# STM32H753.net
KiCad netlist of a schematic drawn in Altium Designer
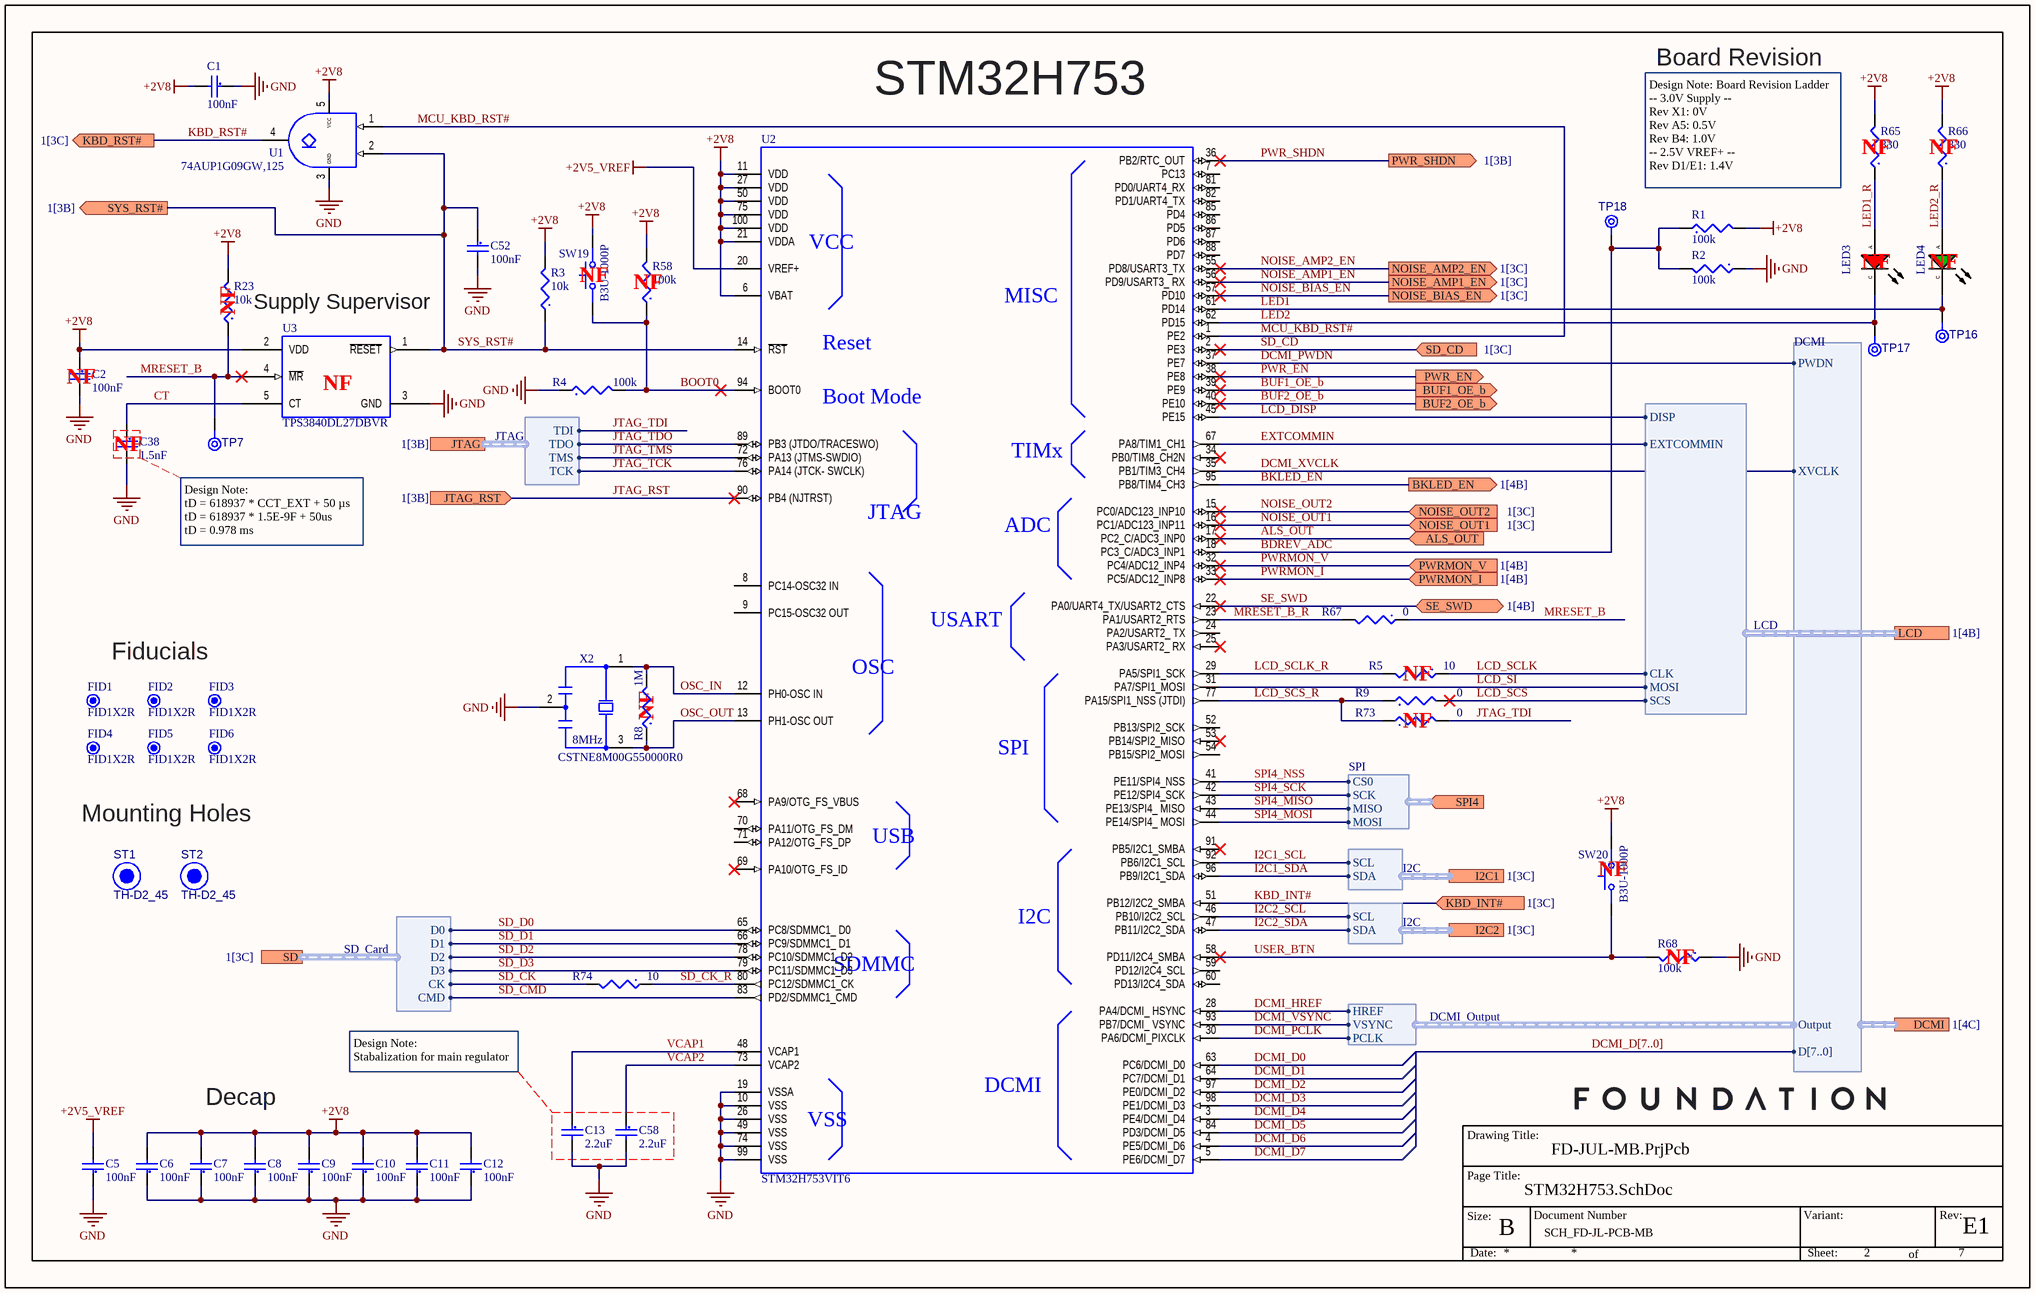
[diagram p0: STM32H753.SchDoc]

(export (version "E")
  (design (tool "Eeschema 10.0.6"))
  (components
    (comp (ref "C1")
      (value "CAP CER 0.1uF 16V 10% X7R 0402")
      (footprint "CAPC0402(1005)55_L")
      (description "0.1µF ±10% 16V Ceramic Capacitor X7R 0402 (1005 Metric)")
      (fields
        (field (name "CAPACITANCE") "100nF")
        (field (name "TOLERANCE") "10%")
        (field (name "VOLTAGE") "16V")
      )
      (libsource (lib "Altium Concord Pro on A365") (part "CAP-NP-2"))
    )
    (comp (ref "C2")
      (value "CAP CER 0.1uF 16V 10% X7R 0402")
      (footprint "CAPC0402(1005)55_L")
      (description "0.1µF ±10% 16V Ceramic Capacitor X7R 0402 (1005 Metric)")
      (fields
        (field (name "CAPACITANCE") "100nF")
        (field (name "VOLTAGE") "16V")
        (field (name "TOLERANCE") "10%")
      )
      (libsource (lib "Altium Concord Pro on A365") (part "CAP-NP-2"))
    )
    (comp (ref "C5")
      (value "CAP CER 0.1uF 16V 10% X7R 0402")
      (footprint "CAPC0402(1005)55_L")
      (description "0.1µF ±10% 16V Ceramic Capacitor X7R 0402 (1005 Metric)")
      (fields
        (field (name "CAPACITANCE") "100nF")
        (field (name "TOLERANCE") "10%")
        (field (name "VOLTAGE") "16V")
      )
      (libsource (lib "Altium Concord Pro on A365") (part "CAP-NP-2"))
    )
    (comp (ref "C6")
      (value "CAP CER 0.1uF 16V 10% X7R 0402")
      (footprint "CAPC0402(1005)55_L")
      (description "0.1µF ±10% 16V Ceramic Capacitor X7R 0402 (1005 Metric)")
      (fields
        (field (name "CAPACITANCE") "100nF")
        (field (name "TOLERANCE") "10%")
        (field (name "VOLTAGE") "16V")
      )
      (libsource (lib "Altium Concord Pro on A365") (part "CAP-NP-2"))
    )
    (comp (ref "C7")
      (value "CAP CER 0.1uF 16V 10% X7R 0402")
      (footprint "CAPC0402(1005)55_L")
      (description "0.1µF ±10% 16V Ceramic Capacitor X7R 0402 (1005 Metric)")
      (fields
        (field (name "CAPACITANCE") "100nF")
        (field (name "TOLERANCE") "10%")
        (field (name "VOLTAGE") "16V")
      )
      (libsource (lib "Altium Concord Pro on A365") (part "CAP-NP-2"))
    )
    (comp (ref "C8")
      (value "CAP CER 0.1uF 16V 10% X7R 0402")
      (footprint "CAPC0402(1005)55_L")
      (description "0.1µF ±10% 16V Ceramic Capacitor X7R 0402 (1005 Metric)")
      (fields
        (field (name "CAPACITANCE") "100nF")
        (field (name "TOLERANCE") "10%")
        (field (name "VOLTAGE") "16V")
      )
      (libsource (lib "Altium Concord Pro on A365") (part "CAP-NP-2"))
    )
    (comp (ref "C9")
      (value "CAP CER 0.1uF 16V 10% X7R 0402")
      (footprint "CAPC0402(1005)55_L")
      (description "0.1µF ±10% 16V Ceramic Capacitor X7R 0402 (1005 Metric)")
      (fields
        (field (name "CAPACITANCE") "100nF")
        (field (name "TOLERANCE") "10%")
        (field (name "VOLTAGE") "16V")
      )
      (libsource (lib "Altium Concord Pro on A365") (part "CAP-NP-2"))
    )
    (comp (ref "C10")
      (value "CAP CER 0.1uF 16V 10% X7R 0402")
      (footprint "CAPC0402(1005)55_L")
      (description "0.1µF ±10% 16V Ceramic Capacitor X7R 0402 (1005 Metric)")
      (fields
        (field (name "CAPACITANCE") "100nF")
        (field (name "TOLERANCE") "10%")
        (field (name "VOLTAGE") "16V")
      )
      (libsource (lib "Altium Concord Pro on A365") (part "CAP-NP-2"))
    )
    (comp (ref "C11")
      (value "CAP CER 0.1uF 16V 10% X7R 0402")
      (footprint "CAPC0402(1005)55_L")
      (description "0.1µF ±10% 16V Ceramic Capacitor X7R 0402 (1005 Metric)")
      (fields
        (field (name "CAPACITANCE") "100nF")
        (field (name "TOLERANCE") "10%")
        (field (name "VOLTAGE") "16V")
      )
      (libsource (lib "Altium Concord Pro on A365") (part "CAP-NP-2"))
    )
    (comp (ref "C12")
      (value "CAP CER 0.1uF 16V 10% X7R 0402")
      (footprint "CAPC0402(1005)55_L")
      (description "0.1µF ±10% 16V Ceramic Capacitor X7R 0402 (1005 Metric)")
      (fields
        (field (name "CAPACITANCE") "100nF")
        (field (name "TOLERANCE") "10%")
        (field (name "VOLTAGE") "16V")
      )
      (libsource (lib "Altium Concord Pro on A365") (part "CAP-NP-2"))
    )
    (comp (ref "C13")
      (value "CAP CER 2.2uF 6.3V 10% X5R 0402")
      (footprint "CAPC0402(1005)55_L")
      (description "2.2µF ±10% 6.3V Ceramic Capacitor X5R 0402 (1005 Metric)")
      (fields (field (name "CAPACITANCE") "2.2uF") (field (name "TOLERANCE") "10%"))
      (libsource (lib "Altium Concord Pro on A365") (part "CAP-NP-2"))
    )
    (comp (ref "C38")
      (value "CAP CER 1500pF 50V 10% X7R 0402")
      (footprint "CAPC0402(1005)55_L")
      (description "1500pF ±10% 50V Ceramic Capacitor X7R 0402 (1005 Metric)")
      (fields
        (field (name "CAPACITANCE") "1.5nF")
        (field (name "VOLTAGE") "50V")
        (field (name "TOLERANCE") "10%")
      )
      (libsource (lib "Altium Concord Pro on A365") (part "CAP-NP-2"))
    )
    (comp (ref "C52")
      (value "CAP CER 0.1uF 16V 10% X7R 0402")
      (footprint "CAPC0402(1005)55_L")
      (description "0.1µF ±10% 16V Ceramic Capacitor X7R 0402 (1005 Metric)")
      (fields
        (field (name "CAPACITANCE") "100nF")
        (field (name "VOLTAGE") "16V")
        (field (name "TOLERANCE") "10%")
      )
      (libsource (lib "Altium Concord Pro on A365") (part "CAP-NP-2"))
    )
    (comp (ref "C58")
      (value "CAP CER 2.2uF 6.3V 10% X5R 0402")
      (footprint "CAPC0402(1005)55_L")
      (description "2.2µF ±10% 6.3V Ceramic Capacitor X5R 0402 (1005 Metric)")
      (fields (field (name "CAPACITANCE") "2.2uF") (field (name "TOLERANCE") "10%"))
      (libsource (lib "Altium Concord Pro on A365") (part "CAP-NP-2"))
    )
    (comp (ref "FID1")
      (value "FID1X2R")
      (footprint "FID1X2R")
      (description "Fiducial - Round 1x2mm")
      (libsource (lib "Altium Concord Pro on A365") (part "FID-R-1"))
    )
    (comp (ref "FID2")
      (value "FID1X2R")
      (footprint "FID1X2R")
      (description "Fiducial - Round 1x2mm")
      (libsource (lib "Altium Concord Pro on A365") (part "FID-R-1"))
    )
    (comp (ref "FID3")
      (value "FID1X2R")
      (footprint "FID1X2R")
      (description "Fiducial - Round 1x2mm")
      (libsource (lib "Altium Concord Pro on A365") (part "FID-R-1"))
    )
    (comp (ref "FID4")
      (value "FID1X2R")
      (footprint "FID1X2R")
      (description "Fiducial - Round 1x2mm")
      (libsource (lib "Altium Concord Pro on A365") (part "FID-R-1"))
    )
    (comp (ref "FID5")
      (value "FID1X2R")
      (footprint "FID1X2R")
      (description "Fiducial - Round 1x2mm")
      (libsource (lib "Altium Concord Pro on A365") (part "FID-R-1"))
    )
    (comp (ref "FID6")
      (value "FID1X2R")
      (footprint "FID1X2R")
      (description "Fiducial - Round 1x2mm")
      (libsource (lib "Altium Concord Pro on A365") (part "FID-R-1"))
    )
    (comp (ref "LED3")
      (value "LTST-C191KRKT")
      (footprint "LEDC0603(1608)65_L")
      (description "Red 631nm LED Indication - Discrete 2V 0603 (1608 Metric)")
      (fields (field (name "VOLTAGE") "2V"))
      (libsource (lib "Altium Concord Pro on A365") (part "LED-RED-AC-2"))
    )
    (comp (ref "LED4")
      (value "LTST-C191KGKT")
      (footprint "LEDC0603(1608)65_L")
      (description "Green 571nm LED Indication - Discrete 2V 0603 (1608 Metric)")
      (libsource (lib "Altium Concord Pro on A365") (part "LED-GREEN-AC-2"))
    )
    (comp (ref "R1")
      (value "RES 100K 1/16W 1% 0402")
      (footprint "RESC0402(1005)_L")
      (description "100 kOhms ±1% 0.063W, 1/16W Chip Resistor 0402 (1005 Metric) Automotive AEC-Q200 Thick Film")
      (fields (field (name "RESISTANCE") "100k") (field (name "TOLERANCE") "1%"))
      (libsource (lib "Altium Concord Pro on A365") (part "RES-2"))
    )
    (comp (ref "R2")
      (value "RES 100K 1/16W 1% 0402")
      (footprint "RESC0402(1005)_L")
      (description "100 kOhms ±1% 0.063W, 1/16W Chip Resistor 0402 (1005 Metric) Automotive AEC-Q200 Thick Film")
      (fields (field (name "RESISTANCE") "100k") (field (name "TOLERANCE") "1%"))
      (libsource (lib "Altium Concord Pro on A365") (part "RES-2"))
    )
    (comp (ref "R3")
      (value "RES 10K 1/16W 1% 0402")
      (footprint "RESC0402(1005)_L")
      (description "10 kOhms ±1% 0.063W, 1/16W Chip Resistor 0402 (1005 Metric)")
      (fields (field (name "RESISTANCE") "10k") (field (name "TOLERANCE") "1%"))
      (libsource (lib "Altium Concord Pro on A365") (part "RES-2"))
    )
    (comp (ref "R4")
      (value "RES 100K 1/16W 1% 0402")
      (footprint "RESC0402(1005)_L")
      (description "100 kOhms ±1% 0.063W, 1/16W Chip Resistor 0402 (1005 Metric) Automotive AEC-Q200 Thick Film")
      (fields (field (name "RESISTANCE") "100k") (field (name "TOLERANCE") "1%"))
      (libsource (lib "Altium Concord Pro on A365") (part "RES-2"))
    )
    (comp (ref "R5")
      (value "RES 10 OHM 1/16W 1% 0402")
      (footprint "RESC0402(1005)_L")
      (description "10 Ohms ±1% 0.063W, 1/16W Chip Resistor 0402 (1005 Metric)")
      (fields (field (name "RESISTANCE") "10") (field (name "TOLERANCE") "1%"))
      (libsource (lib "Altium Concord Pro on A365") (part "RES-2"))
    )
    (comp (ref "R8")
      (value "RES 1M 1/16W 1% 0402")
      (footprint "RESC0402(1005)_L")
      (description "1 MOhms ±1% 0.063W, 1/16W Chip Resistor 0402 (1005 Metric)")
      (fields (field (name "RESISTANCE") "1M") (field (name "TOLERANCE") "1%"))
      (libsource (lib "Altium Concord Pro on A365") (part "RES-2"))
    )
    (comp (ref "R9")
      (value "RES 0 OHM JUMPER 1/16W 0402")
      (footprint "RESC0402(1005)_L")
      (description "0 Ohms Jumper 0.063W, 1/16W Chip Resistor 0402 (1005 Metric)")
      (fields (field (name "RESISTANCE") "0") (field (name "TOLERANCE") "5%"))
      (libsource (lib "Altium Concord Pro on A365") (part "RES-2"))
    )
    (comp (ref "R23")
      (value "RES 10K 1/16W 1% 0402")
      (footprint "RESC0402(1005)_L")
      (description "10 kOhms ±1% 0.063W, 1/16W Chip Resistor 0402 (1005 Metric)")
      (fields (field (name "RESISTANCE") "10k") (field (name "TOLERANCE") "1%"))
      (libsource (lib "Altium Concord Pro on A365") (part "RES-2"))
    )
    (comp (ref "R58")
      (value "RES 100K 1/16W 1% 0402")
      (footprint "RESC0402(1005)_L")
      (description "100 kOhms ±1% 0.063W, 1/16W Chip Resistor 0402 (1005 Metric) Automotive AEC-Q200 Thick Film")
      (fields (field (name "RESISTANCE") "100k") (field (name "TOLERANCE") "1%"))
      (libsource (lib "Altium Concord Pro on A365") (part "RES-2"))
    )
    (comp (ref "R65")
      (value "RES 330 OHM 1/16W 1% 0402")
      (footprint "RESC0402(1005)_L")
      (description "330 Ohms ±1% 0.063W, 1/16W Chip Resistor 0402 (1005 Metric) Moisture Resistant Thick Film")
      (fields (field (name "RESISTANCE") "330") (field (name "TOLERANCE") "1%"))
      (libsource (lib "Altium Concord Pro on A365") (part "RES-2"))
    )
    (comp (ref "R66")
      (value "RES 330 OHM 1/16W 1% 0402")
      (footprint "RESC0402(1005)_L")
      (description "330 Ohms ±1% 0.063W, 1/16W Chip Resistor 0402 (1005 Metric) Moisture Resistant Thick Film")
      (fields (field (name "RESISTANCE") "330") (field (name "TOLERANCE") "1%"))
      (libsource (lib "Altium Concord Pro on A365") (part "RES-2"))
    )
    (comp (ref "R67")
      (value "RES 0 OHM JUMPER 1/16W 0402")
      (footprint "RESC0402(1005)_L")
      (description "0 Ohms Jumper 0.063W, 1/16W Chip Resistor 0402 (1005 Metric)")
      (fields (field (name "RESISTANCE") "0") (field (name "TOLERANCE") "5%"))
      (libsource (lib "Altium Concord Pro on A365") (part "RES-2"))
    )
    (comp (ref "R68")
      (value "RES 100K 1/16W 1% 0402")
      (footprint "RESC0402(1005)_L")
      (description "100 kOhms ±1% 0.063W, 1/16W Chip Resistor 0402 (1005 Metric) Automotive AEC-Q200 Thick Film")
      (fields (field (name "RESISTANCE") "100k") (field (name "TOLERANCE") "1%"))
      (libsource (lib "Altium Concord Pro on A365") (part "RES-2"))
    )
    (comp (ref "R73")
      (value "RES 0 OHM JUMPER 1/16W 0402")
      (footprint "RESC0402(1005)_L")
      (description "0 Ohms Jumper 0.063W, 1/16W Chip Resistor 0402 (1005 Metric)")
      (fields (field (name "RESISTANCE") "0") (field (name "TOLERANCE") "5%"))
      (libsource (lib "Altium Concord Pro on A365") (part "RES-2"))
    )
    (comp (ref "R74")
      (value "RES 10 OHM 1/16W 1% 0402")
      (footprint "RESC0402(1005)_L")
      (description "10 Ohms ±1% 0.063W, 1/16W Chip Resistor 0402 (1005 Metric)")
      (fields (field (name "RESISTANCE") "10") (field (name "TOLERANCE") "1%"))
      (libsource (lib "Altium Concord Pro on A365") (part "RES-2"))
    )
    (comp (ref "ST1")
      (value "TH-D2_45")
      (footprint "TH-D2_54")
      (description "Through Hole, Drill 2.54mm")
      (libsource (lib "Altium Concord Pro on A365") (part "TH"))
    )
    (comp (ref "ST2")
      (value "TH-D2_45")
      (footprint "TH-D2_54")
      (description "Through Hole, Drill 2.54mm")
      (libsource (lib "Altium Concord Pro on A365") (part "TH"))
    )
    (comp (ref "SW19")
      (value "B3U-1000P")
      (footprint "OMRON-B3U-1000P-2_V")
      (description "Tactile Switch SPST-NO Top Actuated Surface Mount")
      (libsource (lib "Altium Concord Pro on A365") (part "TAC-2"))
    )
    (comp (ref "SW20")
      (value "B3U-1000P")
      (footprint "OMRON-B3U-1000P-2_V")
      (description "Tactile Switch SPST-NO Top Actuated Surface Mount")
      (libsource (lib "Altium Concord Pro on A365") (part "TAC-2"))
    )
    (comp (ref "TP7")
      (value "TPAD8R")
      (footprint "TP08R")
      (description "0.8mm round")
      (libsource (lib "Altium Concord Pro on A365") (part "TP-R-1"))
    )
    (comp (ref "TP16")
      (value "TPAD8R")
      (footprint "TP08R")
      (description "0.8mm round")
      (libsource (lib "Altium Concord Pro on A365") (part "TP-R-1"))
    )
    (comp (ref "TP17")
      (value "TPAD8R")
      (footprint "TP08R")
      (description "0.8mm round")
      (libsource (lib "Altium Concord Pro on A365") (part "TP-R-1"))
    )
    (comp (ref "TP18")
      (value "TPAD8R")
      (footprint "TP08R")
      (description "0.8mm round")
      (libsource (lib "Altium Concord Pro on A365") (part "TP-R-1"))
    )
    (comp (ref "U1")
      (value "74AUP1G09GW,125")
      (footprint "NEXP - TSSOP-5_L")
      (description "IC GATE AND 1CH 2-INP 5TSSOP")
      (libsource (lib "Altium Concord Pro on A365") (part "AND-2-12-4-3-OD"))
    )
    (comp (ref "U2")
      (value "STM32H753VIT6")
      (footprint "STM - LQFP-100_L")
      (description "ARM® Cortex®-M7 STM32H7 Microcontroller IC 32-Bit 480MHz 2MB (2M x 8) FLASH 100-LQFP (14x14)")
      (libsource (lib "Altium Concord Pro on A365") (part "STM32H743VIT6"))
    )
    (comp (ref "U3")
      (value "TPS3840DL27DBVR")
      (footprint "SOT-23-5(95)_L")
      (description "Supervisor 2.7V Open Drain 1 Channel SOT-23-5")
      (libsource (lib "Altium Concord Pro on A365") (part "TPS3840DL"))
    )
    (comp (ref "X2")
      (value "CSTNE8M00G550000R0")
      (footprint "MURA - CSTNE_V")
      (description "8MHz Ceramic Resonator Built in Capacitor 33pF ±0.2% 40 Ohms -40°C ~ 85°C Surface Mount")
      (fields (field (name "FREQUENCY") "8MHz"))
      (libsource (lib "Altium Concord Pro on A365") (part "XTAL-3-13-INTC"))
    )
  )
  (nets
    (net (code "8") (name "+2V5_VREF") (class "Default")
      (node (ref "C5") (pin "2") (pinfunction "2_2") (pintype "passive"))
      (node (ref "U2") (pin "20") (pinfunction "VREF+_20") (pintype "power_in"))
    )
    (net (code "9") (name "+2V8") (class "Default")
      (node (ref "C1") (pin "2") (pinfunction "2_2") (pintype "passive"))
      (node (ref "C10") (pin "2") (pinfunction "2_2") (pintype "passive"))
      (node (ref "C11") (pin "2") (pinfunction "2_2") (pintype "passive"))
      (node (ref "C12") (pin "2") (pinfunction "2_2") (pintype "passive"))
      (node (ref "C2") (pin "1") (pinfunction "1_1") (pintype "passive"))
      (node (ref "C6") (pin "2") (pinfunction "2_2") (pintype "passive"))
      (node (ref "C7") (pin "2") (pinfunction "2_2") (pintype "passive"))
      (node (ref "C8") (pin "2") (pinfunction "2_2") (pintype "passive"))
      (node (ref "C9") (pin "2") (pinfunction "2_2") (pintype "passive"))
      (node (ref "R1") (pin "2") (pinfunction "2_2") (pintype "passive"))
      (node (ref "R23") (pin "2") (pinfunction "2_2") (pintype "passive"))
      (node (ref "R3") (pin "2") (pinfunction "2_2") (pintype "passive"))
      (node (ref "R58") (pin "2") (pinfunction "2_2") (pintype "passive"))
      (node (ref "R65") (pin "2") (pinfunction "2_2") (pintype "passive"))
      (node (ref "R66") (pin "2") (pinfunction "2_2") (pintype "passive"))
      (node (ref "SW19") (pin "2") (pinfunction "2_2") (pintype "passive"))
      (node (ref "SW20") (pin "2") (pinfunction "2_2") (pintype "passive"))
      (node (ref "U1") (pin "5") (pinfunction "VCC_5") (pintype "passive"))
      (node (ref "U2") (pin "100") (pinfunction "VDD_100") (pintype "power_in"))
      (node (ref "U2") (pin "11") (pinfunction "VDD_11") (pintype "power_in"))
      (node (ref "U2") (pin "21") (pinfunction "VDDA_21") (pintype "power_in"))
      (node (ref "U2") (pin "27") (pinfunction "VDD_27") (pintype "power_in"))
      (node (ref "U2") (pin "50") (pinfunction "VDD_50") (pintype "power_in"))
      (node (ref "U2") (pin "6") (pinfunction "VBAT_6") (pintype "power_in"))
      (node (ref "U2") (pin "75") (pinfunction "VDD_75") (pintype "power_in"))
      (node (ref "U3") (pin "2") (pinfunction "VDD_2") (pintype "power_in"))
    )
    (net (code "10") (name "/ALS_OUT") (class "Default")
      (node (ref "U2") (pin "17") (pinfunction "PC2_C/ADC3_INP0_17") (pintype "bidirectional+no_connect"))
    )
    (net (code "11") (name "/BDREV_ADC") (class "Default")
      (node (ref "R1") (pin "1") (pinfunction "1_1") (pintype "passive"))
      (node (ref "R2") (pin "2") (pinfunction "2_2") (pintype "passive"))
      (node (ref "TP18") (pin "1") (pinfunction "TP_1") (pintype "passive"))
      (node (ref "U2") (pin "18") (pinfunction "PC3_C/ADC3_INP1_18") (pintype "bidirectional"))
    )
    (net (code "12") (name "/BKLED_EN") (class "Default")
      (node (ref "U2") (pin "95") (pinfunction "PB8/TIM4_CH3_95") (pintype "output"))
    )
    (net (code "13") (name "/BOOT0") (class "Default")
      (node (ref "R4") (pin "2") (pinfunction "2_2") (pintype "passive"))
      (node (ref "R58") (pin "1") (pinfunction "1_1") (pintype "passive"))
      (node (ref "SW19") (pin "1") (pinfunction "1_1") (pintype "passive"))
      (node (ref "U2") (pin "94") (pinfunction "BOOT0_94") (pintype "input"))
    )
    (net (code "14") (name "/BUF1_OE_b") (class "Default")
      (node (ref "U2") (pin "39") (pinfunction "PE9_39") (pintype "bidirectional+no_connect"))
    )
    (net (code "15") (name "/BUF2_OE_b") (class "Default")
      (node (ref "U2") (pin "40") (pinfunction "PE10_40") (pintype "bidirectional+no_connect"))
    )
    (net (code "16") (name "/CT") (class "Default")
      (node (ref "C38") (pin "1") (pinfunction "1_1") (pintype "passive"))
      (node (ref "U3") (pin "5") (pinfunction "CT_5") (pintype "passive"))
    )
    (net (code "17") (name "/DCMI_D0") (class "Default")
      (node (ref "U2") (pin "63") (pinfunction "PC6/DCMI_D0_63") (pintype "input"))
    )
    (net (code "18") (name "/DCMI_D1") (class "Default")
      (node (ref "U2") (pin "64") (pinfunction "PC7/DCMI_D1_64") (pintype "input"))
    )
    (net (code "19") (name "/DCMI_D2") (class "Default")
      (node (ref "U2") (pin "97") (pinfunction "PE0/DCMI_D2_97") (pintype "input"))
    )
    (net (code "20") (name "/DCMI_D3") (class "Default")
      (node (ref "U2") (pin "98") (pinfunction "PE1/DCMI_D3_98") (pintype "input"))
    )
    (net (code "21") (name "/DCMI_D4") (class "Default")
      (node (ref "U2") (pin "3") (pinfunction "PE4/DCMI_D4_3") (pintype "input"))
    )
    (net (code "22") (name "/DCMI_D5") (class "Default")
      (node (ref "U2") (pin "84") (pinfunction "PD3/DCMI_D5_84") (pintype "input"))
    )
    (net (code "23") (name "/DCMI_D6") (class "Default")
      (node (ref "U2") (pin "4") (pinfunction "PE5/DCMI_D6_4") (pintype "input"))
    )
    (net (code "24") (name "/DCMI_D7") (class "Default")
      (node (ref "U2") (pin "5") (pinfunction "PE6/DCMI_D7_5") (pintype "input"))
    )
    (net (code "25") (name "/DCMI_HREF") (class "Default")
      (node (ref "U2") (pin "28") (pinfunction "PA4/DCMI__HSYNC_28") (pintype "input"))
    )
    (net (code "26") (name "/DCMI_PCLK") (class "Default")
      (node (ref "U2") (pin "30") (pinfunction "PA6/DCMI_PIXCLK_30") (pintype "input"))
    )
    (net (code "27") (name "/DCMI_PWDN") (class "Default")
      (node (ref "U2") (pin "37") (pinfunction "PE7_37") (pintype "bidirectional"))
    )
    (net (code "28") (name "/DCMI_VSYNC") (class "Default")
      (node (ref "U2") (pin "93") (pinfunction "PB7/DCMI__VSYNC_93") (pintype "input"))
    )
    (net (code "29") (name "/DCMI_XVCLK") (class "Default")
      (node (ref "U2") (pin "35") (pinfunction "PB1/TIM3_CH4_35") (pintype "output"))
    )
    (net (code "31") (name "/EXTCOMMIN") (class "Default")
      (node (ref "U2") (pin "67") (pinfunction "PA8/TIM1_CH1_67") (pintype "output"))
    )
    (net (code "32") (name "/I2C1_SCL") (class "Default")
      (node (ref "U2") (pin "92") (pinfunction "PB6/I2C1_SCL_92") (pintype "output"))
    )
    (net (code "33") (name "/I2C1_SDA") (class "Default")
      (node (ref "U2") (pin "96") (pinfunction "PB9/I2C1_SDA_96") (pintype "bidirectional"))
    )
    (net (code "34") (name "/I2C2_SCL") (class "Default")
      (node (ref "U2") (pin "46") (pinfunction "PB10/I2C2_SCL_46") (pintype "output"))
    )
    (net (code "35") (name "/I2C2_SDA") (class "Default")
      (node (ref "U2") (pin "47") (pinfunction "PB11/I2C2_SDA_47") (pintype "bidirectional"))
    )
    (net (code "36") (name "/JTAG_RST") (class "Default")
      (node (ref "U2") (pin "90") (pinfunction "PB4_(NJTRST)_90") (pintype "bidirectional+no_connect"))
    )
    (net (code "37") (name "/JTAG_TCK") (class "Default")
      (node (ref "U2") (pin "76") (pinfunction "PA14_(JTCK-_SWCLK)_76") (pintype "bidirectional"))
    )
    (net (code "38") (name "/JTAG_TDI") (class "Default")
      (node (ref "R73") (pin "2") (pinfunction "2_2") (pintype "passive"))
    )
    (net (code "39") (name "/JTAG_TDO") (class "Default")
      (node (ref "U2") (pin "89") (pinfunction "PB3_(JTDO/TRACESWO)_89") (pintype "bidirectional"))
    )
    (net (code "40") (name "/JTAG_TMS") (class "Default")
      (node (ref "U2") (pin "72") (pinfunction "PA13_(JTMS-SWDIO)_72") (pintype "bidirectional"))
    )
    (net (code "41") (name "/KBD_INT#") (class "Default")
      (node (ref "U2") (pin "51") (pinfunction "PB12/I2C2_SMBA_51") (pintype "input"))
    )
    (net (code "42") (name "/KBD_RST#") (class "Default")
      (node (ref "U1") (pin "4") (pinfunction "4_4") (pintype "open_collector"))
    )
    (net (code "43") (name "/LCD_DISP") (class "Default")
      (node (ref "U2") (pin "45") (pinfunction "PE15_45") (pintype "bidirectional"))
    )
    (net (code "44") (name "/LCD_SCLK") (class "Default")
      (node (ref "R5") (pin "1") (pinfunction "1_1") (pintype "passive"))
    )
    (net (code "45") (name "/LCD_SCLK_R") (class "Default")
      (node (ref "R5") (pin "2") (pinfunction "2_2") (pintype "passive"))
      (node (ref "U2") (pin "29") (pinfunction "PA5/SPI1_SCK_29") (pintype "output"))
    )
    (net (code "46") (name "/LCD_SCS") (class "Default")
      (node (ref "R9") (pin "2") (pinfunction "2_2") (pintype "passive+no_connect"))
    )
    (net (code "47") (name "/LCD_SCS_R") (class "Default")
      (node (ref "R73") (pin "1") (pinfunction "1_1") (pintype "passive"))
      (node (ref "R9") (pin "1") (pinfunction "1_1") (pintype "passive"))
      (node (ref "U2") (pin "77") (pinfunction "PA15/SPI1_NSS_(JTDI)_77") (pintype "output"))
    )
    (net (code "48") (name "/LCD_SI") (class "Default")
      (node (ref "U2") (pin "31") (pinfunction "PA7/SPI1_MOSI_31") (pintype "output"))
    )
    (net (code "49") (name "/LED1") (class "Default")
      (node (ref "LED4") (pin "C") (pinfunction "C_C") (pintype "passive"))
      (node (ref "TP16") (pin "1") (pinfunction "TP_1") (pintype "passive"))
      (node (ref "U2") (pin "61") (pinfunction "PD14_61") (pintype "bidirectional"))
    )
    (net (code "50") (name "/LED1_R") (class "Default")
      (node (ref "LED3") (pin "A") (pinfunction "A_A") (pintype "passive"))
      (node (ref "R65") (pin "1") (pinfunction "1_1") (pintype "passive"))
    )
    (net (code "51") (name "/LED2") (class "Default")
      (node (ref "LED3") (pin "C") (pinfunction "C_C") (pintype "passive"))
      (node (ref "TP17") (pin "1") (pinfunction "TP_1") (pintype "passive"))
      (node (ref "U2") (pin "62") (pinfunction "PD15_62") (pintype "bidirectional"))
    )
    (net (code "52") (name "/LED2_R") (class "Default")
      (node (ref "LED4") (pin "A") (pinfunction "A_A") (pintype "passive"))
      (node (ref "R66") (pin "1") (pinfunction "1_1") (pintype "passive"))
    )
    (net (code "53") (name "/MCU_KBD_RST#") (class "Default")
      (node (ref "U1") (pin "1") (pinfunction "1_1") (pintype "input"))
      (node (ref "U2") (pin "1") (pinfunction "PE2_1") (pintype "bidirectional"))
    )
    (net (code "54") (name "/MRESET_B") (class "Default")
      (node (ref "R23") (pin "1") (pinfunction "1_1") (pintype "passive"))
      (node (ref "R67") (pin "1") (pinfunction "1_1") (pintype "passive"))
      (node (ref "TP7") (pin "1") (pinfunction "TP_1") (pintype "passive"))
      (node (ref "U3") (pin "4") (pinfunction "~{MR}_4") (pintype "input"))
    )
    (net (code "55") (name "/MRESET_B_R") (class "Default")
      (node (ref "R67") (pin "2") (pinfunction "2_2") (pintype "passive"))
      (node (ref "U2") (pin "23") (pinfunction "PA1/USART2_RTS_23") (pintype "output"))
    )
    (net (code "56") (name "/NOISE_AMP1_EN") (class "Default")
      (node (ref "U2") (pin "56") (pinfunction "PD9/USART3__RX_56") (pintype "bidirectional+no_connect"))
    )
    (net (code "57") (name "/NOISE_AMP2_EN") (class "Default")
      (node (ref "U2") (pin "55") (pinfunction "PD8/USART3_TX_55") (pintype "bidirectional+no_connect"))
    )
    (net (code "58") (name "/NOISE_BIAS_EN") (class "Default")
      (node (ref "U2") (pin "57") (pinfunction "PD10_57") (pintype "bidirectional+no_connect"))
    )
    (net (code "59") (name "/NOISE_OUT1") (class "Default")
      (node (ref "U2") (pin "16") (pinfunction "PC1/ADC123_INP11_16") (pintype "bidirectional+no_connect"))
    )
    (net (code "60") (name "/NOISE_OUT2") (class "Default")
      (node (ref "U2") (pin "15") (pinfunction "PC0/ADC123_INP10_15") (pintype "bidirectional+no_connect"))
    )
    (net (code "61") (name "/OSC_IN") (class "Default")
      (node (ref "R8") (pin "2") (pinfunction "2_2") (pintype "passive"))
      (node (ref "U2") (pin "12") (pinfunction "PH0-OSC_IN_12") (pintype "passive"))
      (node (ref "X2") (pin "1") (pinfunction "1_1") (pintype "passive"))
    )
    (net (code "62") (name "/OSC_OUT") (class "Default")
      (node (ref "R8") (pin "1") (pinfunction "1_1") (pintype "passive"))
      (node (ref "U2") (pin "13") (pinfunction "PH1-OSC_OUT_13") (pintype "passive"))
      (node (ref "X2") (pin "3") (pinfunction "3_3") (pintype "passive"))
    )
    (net (code "63") (name "/PWRMON_I") (class "Default")
      (node (ref "U2") (pin "33") (pinfunction "PC5/ADC12_INP8_33") (pintype "bidirectional+no_connect"))
    )
    (net (code "64") (name "/PWRMON_V") (class "Default")
      (node (ref "U2") (pin "32") (pinfunction "PC4/ADC12_INP4_32") (pintype "bidirectional+no_connect"))
    )
    (net (code "65") (name "/PWR_EN") (class "Default")
      (node (ref "U2") (pin "38") (pinfunction "PE8_38") (pintype "bidirectional+no_connect"))
    )
    (net (code "66") (name "/PWR_SHDN") (class "Default")
      (node (ref "U2") (pin "36") (pinfunction "PB2/RTC_OUT_36") (pintype "bidirectional+no_connect"))
    )
    (net (code "67") (name "/SD_CD") (class "Default")
      (node (ref "U2") (pin "2") (pinfunction "PE3_2") (pintype "bidirectional+no_connect"))
    )
    (net (code "68") (name "/SD_CK") (class "Default")
      (node (ref "R74") (pin "2") (pinfunction "2_2") (pintype "passive"))
    )
    (net (code "69") (name "/SD_CK_R") (class "Default")
      (node (ref "R74") (pin "1") (pinfunction "1_1") (pintype "passive"))
      (node (ref "U2") (pin "80") (pinfunction "PC12/SDMMC1_CK_80") (pintype "output"))
    )
    (net (code "70") (name "/SD_CMD") (class "Default")
      (node (ref "U2") (pin "83") (pinfunction "PD2/SDMMC1_CMD_83") (pintype "output"))
    )
    (net (code "71") (name "/SD_D0") (class "Default")
      (node (ref "U2") (pin "65") (pinfunction "PC8/SDMMC1__D0_65") (pintype "bidirectional"))
    )
    (net (code "72") (name "/SD_D1") (class "Default")
      (node (ref "U2") (pin "66") (pinfunction "PC9/SDMMC1__D1_66") (pintype "bidirectional"))
    )
    (net (code "73") (name "/SD_D2") (class "Default")
      (node (ref "U2") (pin "78") (pinfunction "PC10/SDMMC1_D2_78") (pintype "bidirectional"))
    )
    (net (code "74") (name "/SD_D3") (class "Default")
      (node (ref "U2") (pin "79") (pinfunction "PC11/SDMMC1_D3_79") (pintype "bidirectional"))
    )
    (net (code "75") (name "/SE_SWD") (class "Default")
      (node (ref "U2") (pin "22") (pinfunction "PA0/UART4_TX/USART2_CTS_22") (pintype "input+no_connect"))
    )
    (net (code "76") (name "/SPI4_MISO") (class "Default")
      (node (ref "U2") (pin "43") (pinfunction "PE13/SPI4__MISO_43") (pintype "input"))
    )
    (net (code "77") (name "/SPI4_MOSI") (class "Default")
      (node (ref "U2") (pin "44") (pinfunction "PE14/SPI4__MOSI_44") (pintype "output"))
    )
    (net (code "78") (name "/SPI4_NSS") (class "Default")
      (node (ref "U2") (pin "41") (pinfunction "PE11/SPI4_NSS_41") (pintype "output"))
    )
    (net (code "79") (name "/SPI4_SCK") (class "Default")
      (node (ref "U2") (pin "42") (pinfunction "PE12/SPI4_SCK_42") (pintype "output"))
    )
    (net (code "80") (name "/SYS_RST#") (class "Default")
      (node (ref "C52") (pin "1") (pinfunction "1_1") (pintype "passive"))
      (node (ref "R3") (pin "1") (pinfunction "1_1") (pintype "passive"))
      (node (ref "U1") (pin "2") (pinfunction "2_2") (pintype "input"))
      (node (ref "U2") (pin "14") (pinfunction "~{RST}_14") (pintype "input"))
      (node (ref "U3") (pin "1") (pinfunction "~{RESET}_1") (pintype "output"))
    )
    (net (code "81") (name "/USER_BTN") (class "Default")
      (node (ref "R68") (pin "2") (pinfunction "2_2") (pintype "passive"))
      (node (ref "SW20") (pin "1") (pinfunction "1_1") (pintype "passive"))
      (node (ref "U2") (pin "58") (pinfunction "PD11/I2C4_SMBA_58") (pintype "input"))
    )
    (net (code "82") (name "/VCAP1") (class "Default")
      (node (ref "C13") (pin "1") (pinfunction "1_1") (pintype "passive"))
      (node (ref "U2") (pin "48") (pinfunction "VCAP1_48") (pintype "passive"))
    )
    (net (code "83") (name "/VCAP2") (class "Default")
      (node (ref "C58") (pin "1") (pinfunction "1_1") (pintype "passive"))
      (node (ref "U2") (pin "73") (pinfunction "VCAP2_73") (pintype "passive"))
    )
    (net (code "91") (name "GND") (class "Default")
      (node (ref "C1") (pin "1") (pinfunction "1_1") (pintype "passive"))
      (node (ref "C10") (pin "1") (pinfunction "1_1") (pintype "passive"))
      (node (ref "C11") (pin "1") (pinfunction "1_1") (pintype "passive"))
      (node (ref "C12") (pin "1") (pinfunction "1_1") (pintype "passive"))
      (node (ref "C13") (pin "2") (pinfunction "2_2") (pintype "passive"))
      (node (ref "C2") (pin "2") (pinfunction "2_2") (pintype "passive"))
      (node (ref "C38") (pin "2") (pinfunction "2_2") (pintype "passive"))
      (node (ref "C5") (pin "1") (pinfunction "1_1") (pintype "passive"))
      (node (ref "C52") (pin "2") (pinfunction "2_2") (pintype "passive"))
      (node (ref "C58") (pin "2") (pinfunction "2_2") (pintype "passive"))
      (node (ref "C6") (pin "1") (pinfunction "1_1") (pintype "passive"))
      (node (ref "C7") (pin "1") (pinfunction "1_1") (pintype "passive"))
      (node (ref "C8") (pin "1") (pinfunction "1_1") (pintype "passive"))
      (node (ref "C9") (pin "1") (pinfunction "1_1") (pintype "passive"))
      (node (ref "R2") (pin "1") (pinfunction "1_1") (pintype "passive"))
      (node (ref "R4") (pin "1") (pinfunction "1_1") (pintype "passive"))
      (node (ref "R68") (pin "1") (pinfunction "1_1") (pintype "passive"))
      (node (ref "U1") (pin "3") (pinfunction "GND_3") (pintype "passive"))
      (node (ref "U2") (pin "10") (pinfunction "VSS_10") (pintype "power_in"))
      (node (ref "U2") (pin "19") (pinfunction "VSSA_19") (pintype "power_in"))
      (node (ref "U2") (pin "26") (pinfunction "VSS_26") (pintype "power_in"))
      (node (ref "U2") (pin "49") (pinfunction "VSS_49") (pintype "power_in"))
      (node (ref "U2") (pin "74") (pinfunction "VSS_74") (pintype "power_in"))
      (node (ref "U2") (pin "99") (pinfunction "VSS_99") (pintype "power_in"))
      (node (ref "U3") (pin "3") (pinfunction "GND_3") (pintype "power_in"))
      (node (ref "X2") (pin "2") (pinfunction "GND_2") (pintype "passive"))
    )
    (net (code "92") (name "unconnected-(U2-PA2{slash}USART2__TX-Pad24)") (class "Default")
      (node (ref "U2") (pin "24") (pinfunction "PA2/USART2__TX_24") (pintype "output"))
    )
    (net (code "93") (name "unconnected-(U2-PA3{slash}USART2__RX-Pad25)") (class "Default")
      (node (ref "U2") (pin "25") (pinfunction "PA3/USART2__RX_25") (pintype "input+no_connect"))
    )
    (net (code "94") (name "unconnected-(U2-PA9{slash}OTG_FS_VBUS-Pad68)") (class "Default")
      (node (ref "U2") (pin "68") (pinfunction "PA9/OTG_FS_VBUS_68") (pintype "input+no_connect"))
    )
    (net (code "95") (name "unconnected-(U2-PA10{slash}OTG_FS_ID-Pad69)") (class "Default")
      (node (ref "U2") (pin "69") (pinfunction "PA10/OTG_FS_ID_69") (pintype "input+no_connect"))
    )
    (net (code "96") (name "unconnected-(U2-PA11{slash}OTG_FS_DM-Pad70)") (class "Default")
      (node (ref "U2") (pin "70") (pinfunction "PA11/OTG_FS_DM_70") (pintype "bidirectional"))
    )
    (net (code "97") (name "unconnected-(U2-PA12{slash}OTG_FS_DP-Pad71)") (class "Default")
      (node (ref "U2") (pin "71") (pinfunction "PA12/OTG_FS_DP_71") (pintype "bidirectional"))
    )
    (net (code "98") (name "unconnected-(U2-PB0{slash}TIM8_CH2N-Pad34)") (class "Default")
      (node (ref "U2") (pin "34") (pinfunction "PB0/TIM8_CH2N_34") (pintype "input+no_connect"))
    )
    (net (code "99") (name "unconnected-(U2-PB5{slash}I2C1_SMBA-Pad91)") (class "Default")
      (node (ref "U2") (pin "91") (pinfunction "PB5/I2C1_SMBA_91") (pintype "input+no_connect"))
    )
    (net (code "100") (name "unconnected-(U2-PB13{slash}SPI2_SCK-Pad52)") (class "Default")
      (node (ref "U2") (pin "52") (pinfunction "PB13/SPI2_SCK_52") (pintype "output"))
    )
    (net (code "101") (name "unconnected-(U2-PB14{slash}SPI2_MISO-Pad53)") (class "Default")
      (node (ref "U2") (pin "53") (pinfunction "PB14/SPI2_MISO_53") (pintype "input+no_connect"))
    )
    (net (code "102") (name "unconnected-(U2-PB15{slash}SPI2_MOSI-Pad54)") (class "Default")
      (node (ref "U2") (pin "54") (pinfunction "PB15/SPI2_MOSI_54") (pintype "output"))
    )
    (net (code "103") (name "unconnected-(U2-PC13-Pad7)") (class "Default")
      (node (ref "U2") (pin "7") (pinfunction "PC13_7") (pintype "bidirectional"))
    )
    (net (code "104") (name "unconnected-(U2-PC14-OSC32_IN-Pad8)") (class "Default")
      (node (ref "U2") (pin "8") (pinfunction "PC14-OSC32_IN_8") (pintype "passive"))
    )
    (net (code "105") (name "unconnected-(U2-PC15-OSC32_OUT-Pad9)") (class "Default")
      (node (ref "U2") (pin "9") (pinfunction "PC15-OSC32_OUT_9") (pintype "passive"))
    )
    (net (code "106") (name "unconnected-(U2-PD0{slash}UART4_RX-Pad81)") (class "Default")
      (node (ref "U2") (pin "81") (pinfunction "PD0/UART4_RX_81") (pintype "bidirectional"))
    )
    (net (code "107") (name "unconnected-(U2-PD1{slash}UART4_TX-Pad82)") (class "Default")
      (node (ref "U2") (pin "82") (pinfunction "PD1/UART4_TX_82") (pintype "bidirectional"))
    )
    (net (code "108") (name "unconnected-(U2-PD4-Pad85)") (class "Default")
      (node (ref "U2") (pin "85") (pinfunction "PD4_85") (pintype "bidirectional"))
    )
    (net (code "109") (name "unconnected-(U2-PD5-Pad86)") (class "Default")
      (node (ref "U2") (pin "86") (pinfunction "PD5_86") (pintype "bidirectional"))
    )
    (net (code "110") (name "unconnected-(U2-PD6-Pad87)") (class "Default")
      (node (ref "U2") (pin "87") (pinfunction "PD6_87") (pintype "bidirectional"))
    )
    (net (code "111") (name "unconnected-(U2-PD7-Pad88)") (class "Default")
      (node (ref "U2") (pin "88") (pinfunction "PD7_88") (pintype "bidirectional"))
    )
    (net (code "112") (name "unconnected-(U2-PD12{slash}I2C4_SCL-Pad59)") (class "Default")
      (node (ref "U2") (pin "59") (pinfunction "PD12/I2C4_SCL_59") (pintype "output"))
    )
    (net (code "113") (name "unconnected-(U2-PD13{slash}I2C4_SDA-Pad60)") (class "Default")
      (node (ref "U2") (pin "60") (pinfunction "PD13/I2C4_SDA_60") (pintype "bidirectional"))
    )
  )
)
